# AFE1-2.net
KiCad netlist of a schematic drawn in Altium Designer
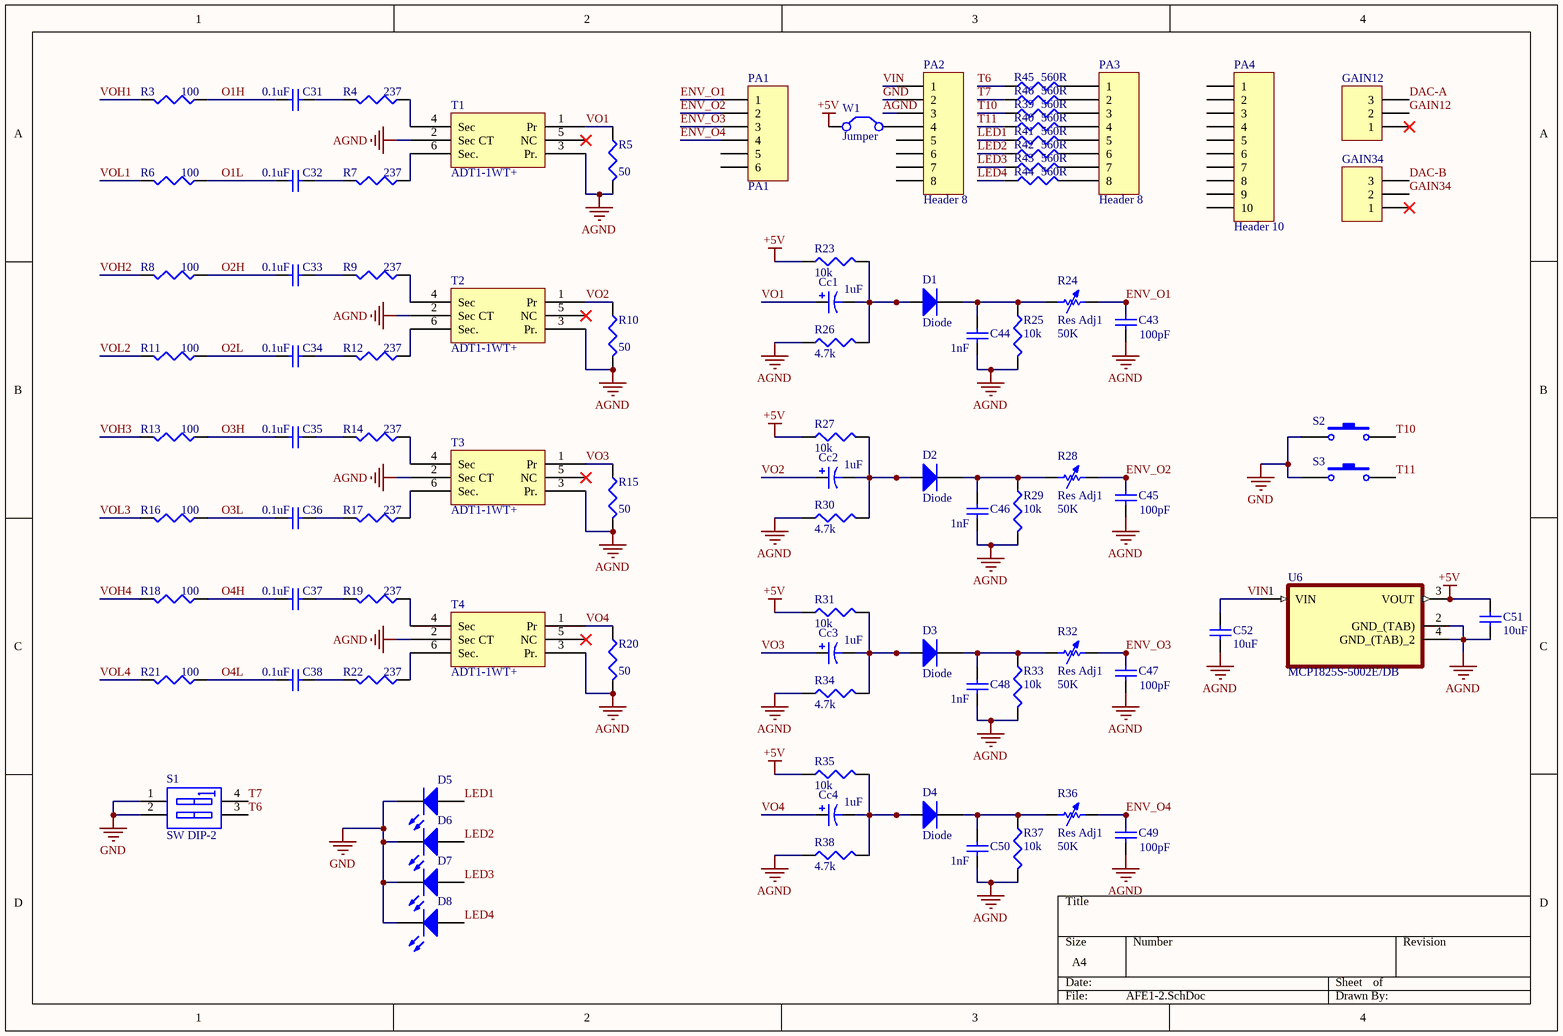
[diagram p0: AFE1-2.SchDoc]

(export (version "E")
  (design (tool "Eeschema 10.0.6"))
  (components
    (comp (ref "C31")
      (value "0.1uF")
      (footprint "1608[0603]")
      (description "Capacitor (Semiconductor SIM Model)")
      (fields (field (name "PUBLISHER") "Altium Limited"))
      (libsource (lib "Miscellaneous Devices") (part "Cap Semi"))
    )
    (comp (ref "C32")
      (value "0.1uF")
      (footprint "1608[0603]")
      (description "Capacitor (Semiconductor SIM Model)")
      (fields (field (name "PUBLISHER") "Altium Limited"))
      (libsource (lib "Miscellaneous Devices") (part "Cap Semi"))
    )
    (comp (ref "C33")
      (value "0.1uF")
      (footprint "1608[0603]")
      (description "Capacitor (Semiconductor SIM Model)")
      (fields (field (name "PUBLISHER") "Altium Limited"))
      (libsource (lib "Miscellaneous Devices") (part "Cap Semi"))
    )
    (comp (ref "C34")
      (value "0.1uF")
      (footprint "1608[0603]")
      (description "Capacitor (Semiconductor SIM Model)")
      (fields (field (name "PUBLISHER") "Altium Limited"))
      (libsource (lib "Miscellaneous Devices") (part "Cap Semi"))
    )
    (comp (ref "C35")
      (value "0.1uF")
      (footprint "1608[0603]")
      (description "Capacitor (Semiconductor SIM Model)")
      (fields (field (name "PUBLISHER") "Altium Limited"))
      (libsource (lib "Miscellaneous Devices") (part "Cap Semi"))
    )
    (comp (ref "C36")
      (value "0.1uF")
      (footprint "1608[0603]")
      (description "Capacitor (Semiconductor SIM Model)")
      (fields (field (name "PUBLISHER") "Altium Limited"))
      (libsource (lib "Miscellaneous Devices") (part "Cap Semi"))
    )
    (comp (ref "C37")
      (value "0.1uF")
      (footprint "1608[0603]")
      (description "Capacitor (Semiconductor SIM Model)")
      (fields (field (name "PUBLISHER") "Altium Limited"))
      (libsource (lib "Miscellaneous Devices") (part "Cap Semi"))
    )
    (comp (ref "C38")
      (value "0.1uF")
      (footprint "1608[0603]")
      (description "Capacitor (Semiconductor SIM Model)")
      (fields (field (name "PUBLISHER") "Altium Limited"))
      (libsource (lib "Miscellaneous Devices") (part "Cap Semi"))
    )
    (comp (ref "C43")
      (value "100pF")
      (footprint "1608[0603]")
      (description "Capacitor (Semiconductor SIM Model)")
      (fields (field (name "PUBLISHER") "Altium Limited"))
      (libsource (lib "Miscellaneous Devices") (part "Cap Semi"))
    )
    (comp (ref "C44")
      (value "1nF")
      (footprint "1608[0603]")
      (description "Capacitor (Semiconductor SIM Model)")
      (fields (field (name "PUBLISHER") "Altium Limited"))
      (libsource (lib "Miscellaneous Devices") (part "Cap Semi"))
    )
    (comp (ref "C45")
      (value "100pF")
      (footprint "1608[0603]")
      (description "Capacitor (Semiconductor SIM Model)")
      (fields (field (name "PUBLISHER") "Altium Limited"))
      (libsource (lib "Miscellaneous Devices") (part "Cap Semi"))
    )
    (comp (ref "C46")
      (value "1nF")
      (footprint "1608[0603]")
      (description "Capacitor (Semiconductor SIM Model)")
      (fields (field (name "PUBLISHER") "Altium Limited"))
      (libsource (lib "Miscellaneous Devices") (part "Cap Semi"))
    )
    (comp (ref "C47")
      (value "100pF")
      (footprint "1608[0603]")
      (description "Capacitor (Semiconductor SIM Model)")
      (fields (field (name "PUBLISHER") "Altium Limited"))
      (libsource (lib "Miscellaneous Devices") (part "Cap Semi"))
    )
    (comp (ref "C48")
      (value "1nF")
      (footprint "1608[0603]")
      (description "Capacitor (Semiconductor SIM Model)")
      (fields (field (name "PUBLISHER") "Altium Limited"))
      (libsource (lib "Miscellaneous Devices") (part "Cap Semi"))
    )
    (comp (ref "C49")
      (value "100pF")
      (footprint "1608[0603]")
      (description "Capacitor (Semiconductor SIM Model)")
      (fields (field (name "PUBLISHER") "Altium Limited"))
      (libsource (lib "Miscellaneous Devices") (part "Cap Semi"))
    )
    (comp (ref "C50")
      (value "1nF")
      (footprint "1608[0603]")
      (description "Capacitor (Semiconductor SIM Model)")
      (fields (field (name "PUBLISHER") "Altium Limited"))
      (libsource (lib "Miscellaneous Devices") (part "Cap Semi"))
    )
    (comp (ref "C51")
      (value "10uF")
      (footprint "6-0805_L")
      (description "Capacitor (Semiconductor SIM Model)")
      (fields (field (name "PUBLISHER") "Altium Limited"))
      (libsource (lib "Miscellaneous Devices") (part "Cap Semi"))
    )
    (comp (ref "C52")
      (value "10uF")
      (footprint "6-0805_L")
      (description "Capacitor (Semiconductor SIM Model)")
      (fields (field (name "PUBLISHER") "Altium Limited"))
      (libsource (lib "Miscellaneous Devices") (part "Cap Semi"))
    )
    (comp (ref "Cc1")
      (value "1uF")
      (footprint "C0805")
      (description "Polarized Capacitor (Surface Mount)")
      (fields (field (name "PUBLISHER") "Altium Limited"))
      (libsource (lib "Miscellaneous Devices") (part "Cap Pol3"))
    )
    (comp (ref "Cc2")
      (value "1uF")
      (footprint "C0805")
      (description "Polarized Capacitor (Surface Mount)")
      (fields (field (name "PUBLISHER") "Altium Limited"))
      (libsource (lib "Miscellaneous Devices") (part "Cap Pol3"))
    )
    (comp (ref "Cc3")
      (value "1uF")
      (footprint "C0805")
      (description "Polarized Capacitor (Surface Mount)")
      (fields (field (name "PUBLISHER") "Altium Limited"))
      (libsource (lib "Miscellaneous Devices") (part "Cap Pol3"))
    )
    (comp (ref "Cc4")
      (value "1uF")
      (footprint "C0805")
      (description "Polarized Capacitor (Surface Mount)")
      (fields (field (name "PUBLISHER") "Altium Limited"))
      (libsource (lib "Miscellaneous Devices") (part "Cap Pol3"))
    )
    (comp (ref "D1")
      (value "Diode")
      (footprint "Miscellaneous Devices:6-0805_L")
      (description "Default Diode")
      (fields (field (name "PUBLISHER") "Altium Limited"))
      (libsource (lib "Miscellaneous Devices") (part "Diode"))
    )
    (comp (ref "D2")
      (value "Diode")
      (footprint "Miscellaneous Devices:6-0805_L")
      (description "Default Diode")
      (fields (field (name "PUBLISHER") "Altium Limited"))
      (libsource (lib "Miscellaneous Devices") (part "Diode"))
    )
    (comp (ref "D3")
      (value "Diode")
      (footprint "Miscellaneous Devices:6-0805_L")
      (description "Default Diode")
      (fields (field (name "PUBLISHER") "Altium Limited"))
      (libsource (lib "Miscellaneous Devices") (part "Diode"))
    )
    (comp (ref "D4")
      (value "Diode")
      (footprint "Miscellaneous Devices:6-0805_L")
      (description "Default Diode")
      (fields (field (name "PUBLISHER") "Altium Limited"))
      (libsource (lib "Miscellaneous Devices") (part "Diode"))
    )
    (comp (ref "D5")
      (value "~")
      (footprint "6-0805_N")
      (description "Typical BLUE SiC LED")
      (fields (field (name "PUBLISHER") "Altium Limited"))
      (libsource (lib "Miscellaneous Devices") (part "LED3"))
    )
    (comp (ref "D6")
      (value "~")
      (footprint "6-0805_N")
      (description "Typical BLUE SiC LED")
      (fields (field (name "PUBLISHER") "Altium Limited"))
      (libsource (lib "Miscellaneous Devices") (part "LED3"))
    )
    (comp (ref "D7")
      (value "~")
      (footprint "6-0805_N")
      (description "Typical BLUE SiC LED")
      (fields (field (name "PUBLISHER") "Altium Limited"))
      (libsource (lib "Miscellaneous Devices") (part "LED3"))
    )
    (comp (ref "D8")
      (value "~")
      (footprint "6-0805_N")
      (description "Typical BLUE SiC LED")
      (fields (field (name "PUBLISHER") "Altium Limited"))
      (libsource (lib "Miscellaneous Devices") (part "LED3"))
    )
    (comp (ref "GAIN12")
      (value "~")
      (footprint "HDR1X3")
      (description "Header, 3-Pin")
      (fields (field (name "PUBLISHER") "Altium Limited"))
      (libsource (lib "Miscellaneous Connectors") (part "Header 3"))
    )
    (comp (ref "GAIN34")
      (value "~")
      (footprint "HDR1X3")
      (description "Header, 3-Pin")
      (fields (field (name "PUBLISHER") "Altium Limited"))
      (libsource (lib "Miscellaneous Connectors") (part "Header 3"))
    )
    (comp (ref "PA1")
      (value "PA1")
      (footprint "HDR1X6")
      (description "Header, 6-Pin")
      (fields (field (name "PUBLISHER") "Altium Limited"))
      (libsource (lib "Miscellaneous Connectors") (part "Header 6"))
    )
    (comp (ref "PA2")
      (value "Header 8")
      (footprint "HDR1X8")
      (description "Header, 8-Pin")
      (fields (field (name "PUBLISHER") "Altium Limited"))
      (libsource (lib "Miscellaneous Connectors") (part "Header 8"))
    )
    (comp (ref "PA3")
      (value "Header 8")
      (footprint "HDR1X8")
      (description "Header, 8-Pin")
      (fields (field (name "PUBLISHER") "Altium Limited"))
      (libsource (lib "Miscellaneous Connectors") (part "Header 8"))
    )
    (comp (ref "PA4")
      (value "Header 10")
      (footprint "HDR1X10")
      (description "Header, 10-Pin")
      (fields (field (name "PUBLISHER") "Altium Limited"))
      (libsource (lib "Miscellaneous Connectors") (part "Header 10"))
    )
    (comp (ref "R3")
      (value "100")
      (footprint "J1-0603")
      (description "Resistor")
      (fields (field (name "PUBLISHER") "Altium Limited"))
      (libsource (lib "Miscellaneous Devices") (part "Res3"))
    )
    (comp (ref "R4")
      (value "237")
      (footprint "J1-0603")
      (description "Resistor")
      (fields (field (name "PUBLISHER") "Altium Limited"))
      (libsource (lib "Miscellaneous Devices") (part "Res3"))
    )
    (comp (ref "R5")
      (value "50")
      (footprint "J1-0603")
      (description "Resistor")
      (fields (field (name "PUBLISHER") "Altium Limited"))
      (libsource (lib "Miscellaneous Devices") (part "Res3"))
    )
    (comp (ref "R6")
      (value "100")
      (footprint "J1-0603")
      (description "Resistor")
      (fields (field (name "PUBLISHER") "Altium Limited"))
      (libsource (lib "Miscellaneous Devices") (part "Res3"))
    )
    (comp (ref "R7")
      (value "237")
      (footprint "J1-0603")
      (description "Resistor")
      (fields (field (name "PUBLISHER") "Altium Limited"))
      (libsource (lib "Miscellaneous Devices") (part "Res3"))
    )
    (comp (ref "R8")
      (value "100")
      (footprint "J1-0603")
      (description "Resistor")
      (fields (field (name "PUBLISHER") "Altium Limited"))
      (libsource (lib "Miscellaneous Devices") (part "Res3"))
    )
    (comp (ref "R9")
      (value "237")
      (footprint "J1-0603")
      (description "Resistor")
      (fields (field (name "PUBLISHER") "Altium Limited"))
      (libsource (lib "Miscellaneous Devices") (part "Res3"))
    )
    (comp (ref "R10")
      (value "50")
      (footprint "J1-0603")
      (description "Resistor")
      (fields (field (name "PUBLISHER") "Altium Limited"))
      (libsource (lib "Miscellaneous Devices") (part "Res3"))
    )
    (comp (ref "R11")
      (value "100")
      (footprint "J1-0603")
      (description "Resistor")
      (fields (field (name "PUBLISHER") "Altium Limited"))
      (libsource (lib "Miscellaneous Devices") (part "Res3"))
    )
    (comp (ref "R12")
      (value "237")
      (footprint "J1-0603")
      (description "Resistor")
      (fields (field (name "PUBLISHER") "Altium Limited"))
      (libsource (lib "Miscellaneous Devices") (part "Res3"))
    )
    (comp (ref "R13")
      (value "100")
      (footprint "J1-0603")
      (description "Resistor")
      (fields (field (name "PUBLISHER") "Altium Limited"))
      (libsource (lib "Miscellaneous Devices") (part "Res3"))
    )
    (comp (ref "R14")
      (value "237")
      (footprint "J1-0603")
      (description "Resistor")
      (fields (field (name "PUBLISHER") "Altium Limited"))
      (libsource (lib "Miscellaneous Devices") (part "Res3"))
    )
    (comp (ref "R15")
      (value "50")
      (footprint "J1-0603")
      (description "Resistor")
      (fields (field (name "PUBLISHER") "Altium Limited"))
      (libsource (lib "Miscellaneous Devices") (part "Res3"))
    )
    (comp (ref "R16")
      (value "100")
      (footprint "J1-0603")
      (description "Resistor")
      (fields (field (name "PUBLISHER") "Altium Limited"))
      (libsource (lib "Miscellaneous Devices") (part "Res3"))
    )
    (comp (ref "R17")
      (value "237")
      (footprint "J1-0603")
      (description "Resistor")
      (fields (field (name "PUBLISHER") "Altium Limited"))
      (libsource (lib "Miscellaneous Devices") (part "Res3"))
    )
    (comp (ref "R18")
      (value "100")
      (footprint "J1-0603")
      (description "Resistor")
      (fields (field (name "PUBLISHER") "Altium Limited"))
      (libsource (lib "Miscellaneous Devices") (part "Res3"))
    )
    (comp (ref "R19")
      (value "237")
      (footprint "J1-0603")
      (description "Resistor")
      (fields (field (name "PUBLISHER") "Altium Limited"))
      (libsource (lib "Miscellaneous Devices") (part "Res3"))
    )
    (comp (ref "R20")
      (value "50")
      (footprint "J1-0603")
      (description "Resistor")
      (fields (field (name "PUBLISHER") "Altium Limited"))
      (libsource (lib "Miscellaneous Devices") (part "Res3"))
    )
    (comp (ref "R21")
      (value "100")
      (footprint "J1-0603")
      (description "Resistor")
      (fields (field (name "PUBLISHER") "Altium Limited"))
      (libsource (lib "Miscellaneous Devices") (part "Res3"))
    )
    (comp (ref "R22")
      (value "237")
      (footprint "J1-0603")
      (description "Resistor")
      (fields (field (name "PUBLISHER") "Altium Limited"))
      (libsource (lib "Miscellaneous Devices") (part "Res3"))
    )
    (comp (ref "R23")
      (value "10k")
      (footprint "J1-0603")
      (description "Resistor")
      (fields (field (name "PUBLISHER") "Altium Limited"))
      (libsource (lib "Miscellaneous Devices") (part "Res3"))
    )
    (comp (ref "R24")
      (value "Res Adj1")
      (footprint "RESC2012M")
      (description "Variable Resistor")
      (fields (field (name "ALTIUM_VALUE") "50K") (field (name "PUBLISHER") "Altium Limited"))
      (libsource (lib "Miscellaneous Devices") (part "Res Adj1"))
    )
    (comp (ref "R25")
      (value "10k")
      (footprint "J1-0603")
      (description "Resistor")
      (fields (field (name "PUBLISHER") "Altium Limited"))
      (libsource (lib "Miscellaneous Devices") (part "Res3"))
    )
    (comp (ref "R26")
      (value "4.7k")
      (footprint "J1-0603")
      (description "Resistor")
      (fields (field (name "PUBLISHER") "Altium Limited"))
      (libsource (lib "Miscellaneous Devices") (part "Res3"))
    )
    (comp (ref "R27")
      (value "10k")
      (footprint "J1-0603")
      (description "Resistor")
      (fields (field (name "PUBLISHER") "Altium Limited"))
      (libsource (lib "Miscellaneous Devices") (part "Res3"))
    )
    (comp (ref "R28")
      (value "Res Adj1")
      (footprint "RESC2012M")
      (description "Variable Resistor")
      (fields (field (name "ALTIUM_VALUE") "50K") (field (name "PUBLISHER") "Altium Limited"))
      (libsource (lib "Miscellaneous Devices") (part "Res Adj1"))
    )
    (comp (ref "R29")
      (value "10k")
      (footprint "J1-0603")
      (description "Resistor")
      (fields (field (name "PUBLISHER") "Altium Limited"))
      (libsource (lib "Miscellaneous Devices") (part "Res3"))
    )
    (comp (ref "R30")
      (value "4.7k")
      (footprint "J1-0603")
      (description "Resistor")
      (fields (field (name "PUBLISHER") "Altium Limited"))
      (libsource (lib "Miscellaneous Devices") (part "Res3"))
    )
    (comp (ref "R31")
      (value "10k")
      (footprint "J1-0603")
      (description "Resistor")
      (fields (field (name "PUBLISHER") "Altium Limited"))
      (libsource (lib "Miscellaneous Devices") (part "Res3"))
    )
    (comp (ref "R32")
      (value "Res Adj1")
      (footprint "RESC2012M")
      (description "Variable Resistor")
      (fields (field (name "ALTIUM_VALUE") "50K") (field (name "PUBLISHER") "Altium Limited"))
      (libsource (lib "Miscellaneous Devices") (part "Res Adj1"))
    )
    (comp (ref "R33")
      (value "10k")
      (footprint "J1-0603")
      (description "Resistor")
      (fields (field (name "PUBLISHER") "Altium Limited"))
      (libsource (lib "Miscellaneous Devices") (part "Res3"))
    )
    (comp (ref "R34")
      (value "4.7k")
      (footprint "J1-0603")
      (description "Resistor")
      (fields (field (name "PUBLISHER") "Altium Limited"))
      (libsource (lib "Miscellaneous Devices") (part "Res3"))
    )
    (comp (ref "R35")
      (value "10k")
      (footprint "J1-0603")
      (description "Resistor")
      (fields (field (name "PUBLISHER") "Altium Limited"))
      (libsource (lib "Miscellaneous Devices") (part "Res3"))
    )
    (comp (ref "R36")
      (value "Res Adj1")
      (footprint "RESC2012M")
      (description "Variable Resistor")
      (fields (field (name "ALTIUM_VALUE") "50K") (field (name "PUBLISHER") "Altium Limited"))
      (libsource (lib "Miscellaneous Devices") (part "Res Adj1"))
    )
    (comp (ref "R37")
      (value "10k")
      (footprint "J1-0603")
      (description "Resistor")
      (fields (field (name "PUBLISHER") "Altium Limited"))
      (libsource (lib "Miscellaneous Devices") (part "Res3"))
    )
    (comp (ref "R38")
      (value "4.7k")
      (footprint "J1-0603")
      (description "Resistor")
      (fields (field (name "PUBLISHER") "Altium Limited"))
      (libsource (lib "Miscellaneous Devices") (part "Res3"))
    )
    (comp (ref "R39")
      (value "560R")
      (footprint "J1-0603")
      (description "Resistor")
      (fields (field (name "PUBLISHER") "Altium Limited"))
      (libsource (lib "Miscellaneous Devices") (part "Res3"))
    )
    (comp (ref "R40")
      (value "560R")
      (footprint "J1-0603")
      (description "Resistor")
      (fields (field (name "PUBLISHER") "Altium Limited"))
      (libsource (lib "Miscellaneous Devices") (part "Res3"))
    )
    (comp (ref "R41")
      (value "560R")
      (footprint "J1-0603")
      (description "Resistor")
      (fields (field (name "PUBLISHER") "Altium Limited"))
      (libsource (lib "Miscellaneous Devices") (part "Res3"))
    )
    (comp (ref "R42")
      (value "560R")
      (footprint "J1-0603")
      (description "Resistor")
      (fields (field (name "PUBLISHER") "Altium Limited"))
      (libsource (lib "Miscellaneous Devices") (part "Res3"))
    )
    (comp (ref "R43")
      (value "560R")
      (footprint "J1-0603")
      (description "Resistor")
      (fields (field (name "PUBLISHER") "Altium Limited"))
      (libsource (lib "Miscellaneous Devices") (part "Res3"))
    )
    (comp (ref "R44")
      (value "560R")
      (footprint "J1-0603")
      (description "Resistor")
      (fields (field (name "PUBLISHER") "Altium Limited"))
      (libsource (lib "Miscellaneous Devices") (part "Res3"))
    )
    (comp (ref "R45")
      (value "560R")
      (footprint "J1-0603")
      (description "Resistor")
      (fields (field (name "PUBLISHER") "Altium Limited"))
      (libsource (lib "Miscellaneous Devices") (part "Res3"))
    )
    (comp (ref "R46")
      (value "560R")
      (footprint "J1-0603")
      (description "Resistor")
      (fields (field (name "PUBLISHER") "Altium Limited"))
      (libsource (lib "Miscellaneous Devices") (part "Res3"))
    )
    (comp (ref "S1")
      (value "SW DIP-2")
      (footprint "DIP-4")
      (description "DIP Switch, 2 Position, SPST")
      (fields (field (name "PUBLISHER") "Altium Limited"))
      (libsource (lib "Miscellaneous Devices") (part "SW DIP-2"))
    )
    (comp (ref "S2")
      (value "~")
      (footprint "PTS525SM08SMTR2LFS")
      (description "Switch")
      (fields (field (name "PUBLISHER") "Altium Limited"))
      (libsource (lib "Miscellaneous Devices") (part "SW-PB"))
    )
    (comp (ref "S3")
      (value "~")
      (footprint "PTS525SM08SMTR2LFS")
      (description "Switch")
      (fields (field (name "PUBLISHER") "Altium Limited"))
      (libsource (lib "Miscellaneous Devices") (part "SW-PB"))
    )
    (comp (ref "T1")
      (value "ADT1-1WT+")
      (footprint "ADT1-1WT+")
      (libsource (lib "ADT1-1WT+") (part "ADT1-1WT+"))
    )
    (comp (ref "T2")
      (value "ADT1-1WT+")
      (footprint "ADT1-1WT+")
      (libsource (lib "ADT1-1WT+") (part "ADT1-1WT+"))
    )
    (comp (ref "T3")
      (value "ADT1-1WT+")
      (footprint "ADT1-1WT+")
      (libsource (lib "ADT1-1WT+") (part "ADT1-1WT+"))
    )
    (comp (ref "T4")
      (value "ADT1-1WT+")
      (footprint "ADT1-1WT+")
      (libsource (lib "ADT1-1WT+") (part "ADT1-1WT+"))
    )
    (comp (ref "U6")
      (value "MCP1825S-5002E/DB")
      (footprint "MCP1825S-5002E_DB:SOT230P700X180-4N")
      (fields (field (name "MF") "{'manufacturer': u'Microchip'}"))
      (libsource (lib "*") (part "MCP1825S-5002E/DB"))
    )
    (comp (ref "W1")
      (value "Jumper")
      (footprint "RAD-0.1")
      (description "Jumper Wire")
      (fields (field (name "PUBLISHER") "Altium Limited"))
      (libsource (lib "Miscellaneous Devices") (part "Jumper"))
    )
  )
  (nets
    (net (code "1") (name "+5V") (class "Default")
      (node (ref "C51") (pin "1") (pinfunction "1_1") (pintype "passive"))
      (node (ref "R23") (pin "1") (pinfunction "1_1") (pintype "passive"))
      (node (ref "R27") (pin "1") (pinfunction "1_1") (pintype "passive"))
      (node (ref "R31") (pin "1") (pinfunction "1_1") (pintype "passive"))
      (node (ref "R35") (pin "1") (pinfunction "1_1") (pintype "passive"))
      (node (ref "U6") (pin "3") (pinfunction "VOUT_3") (pintype "output"))
      (node (ref "W1") (pin "1") (pinfunction "C1_1") (pintype "passive"))
    )
    (net (code "2") (name "/DAC-A") (class "Default")
      (node (ref "GAIN12") (pin "3") (pinfunction "3_3") (pintype "passive"))
    )
    (net (code "3") (name "/DAC-B") (class "Default")
      (node (ref "GAIN34") (pin "3") (pinfunction "3_3") (pintype "passive"))
    )
    (net (code "4") (name "/ENV_O1") (class "Default")
      (node (ref "C43") (pin "1") (pinfunction "1_1") (pintype "passive"))
      (node (ref "PA1") (pin "1") (pinfunction "1_1") (pintype "passive"))
      (node (ref "R24") (pin "2") (pinfunction "2_2") (pintype "passive"))
    )
    (net (code "5") (name "/ENV_O2") (class "Default")
      (node (ref "C45") (pin "1") (pinfunction "1_1") (pintype "passive"))
      (node (ref "PA1") (pin "2") (pinfunction "2_2") (pintype "passive"))
      (node (ref "R28") (pin "2") (pinfunction "2_2") (pintype "passive"))
    )
    (net (code "6") (name "/ENV_O3") (class "Default")
      (node (ref "C47") (pin "1") (pinfunction "1_1") (pintype "passive"))
      (node (ref "PA1") (pin "3") (pinfunction "3_3") (pintype "passive"))
      (node (ref "R32") (pin "2") (pinfunction "2_2") (pintype "passive"))
    )
    (net (code "7") (name "/ENV_O4") (class "Default")
      (node (ref "C49") (pin "1") (pinfunction "1_1") (pintype "passive"))
      (node (ref "PA1") (pin "4") (pinfunction "4_4") (pintype "passive"))
      (node (ref "R36") (pin "2") (pinfunction "2_2") (pintype "passive"))
    )
    (net (code "8") (name "/GAIN12") (class "Default")
      (node (ref "GAIN12") (pin "2") (pinfunction "2_2") (pintype "passive"))
    )
    (net (code "9") (name "/GAIN34") (class "Default")
      (node (ref "GAIN34") (pin "2") (pinfunction "2_2") (pintype "passive"))
    )
    (net (code "10") (name "/LED1") (class "Default")
      (node (ref "D5") (pin "1") (pinfunction "A_1") (pintype "passive"))
      (node (ref "R41") (pin "1") (pinfunction "1_1") (pintype "passive"))
    )
    (net (code "11") (name "/LED2") (class "Default")
      (node (ref "D6") (pin "1") (pinfunction "A_1") (pintype "passive"))
      (node (ref "R42") (pin "1") (pinfunction "1_1") (pintype "passive"))
    )
    (net (code "12") (name "/LED3") (class "Default")
      (node (ref "D7") (pin "1") (pinfunction "A_1") (pintype "passive"))
      (node (ref "R43") (pin "1") (pinfunction "1_1") (pintype "passive"))
    )
    (net (code "13") (name "/LED4") (class "Default")
      (node (ref "D8") (pin "1") (pinfunction "A_1") (pintype "passive"))
      (node (ref "R44") (pin "1") (pinfunction "1_1") (pintype "passive"))
    )
    (net (code "14") (name "/O1H") (class "Default")
      (node (ref "C31") (pin "1") (pinfunction "1_1") (pintype "passive"))
      (node (ref "R3") (pin "1") (pinfunction "1_1") (pintype "passive"))
    )
    (net (code "15") (name "/O1L") (class "Default")
      (node (ref "C32") (pin "1") (pinfunction "1_1") (pintype "passive"))
      (node (ref "R6") (pin "1") (pinfunction "1_1") (pintype "passive"))
    )
    (net (code "16") (name "/O2H") (class "Default")
      (node (ref "C33") (pin "1") (pinfunction "1_1") (pintype "passive"))
      (node (ref "R8") (pin "1") (pinfunction "1_1") (pintype "passive"))
    )
    (net (code "17") (name "/O2L") (class "Default")
      (node (ref "C34") (pin "1") (pinfunction "1_1") (pintype "passive"))
      (node (ref "R11") (pin "1") (pinfunction "1_1") (pintype "passive"))
    )
    (net (code "18") (name "/O3H") (class "Default")
      (node (ref "C35") (pin "1") (pinfunction "1_1") (pintype "passive"))
      (node (ref "R13") (pin "1") (pinfunction "1_1") (pintype "passive"))
    )
    (net (code "19") (name "/O3L") (class "Default")
      (node (ref "C36") (pin "1") (pinfunction "1_1") (pintype "passive"))
      (node (ref "R16") (pin "1") (pinfunction "1_1") (pintype "passive"))
    )
    (net (code "20") (name "/O4H") (class "Default")
      (node (ref "C37") (pin "1") (pinfunction "1_1") (pintype "passive"))
      (node (ref "R18") (pin "1") (pinfunction "1_1") (pintype "passive"))
    )
    (net (code "21") (name "/O4L") (class "Default")
      (node (ref "C38") (pin "1") (pinfunction "1_1") (pintype "passive"))
      (node (ref "R21") (pin "1") (pinfunction "1_1") (pintype "passive"))
    )
    (net (code "22") (name "/T6") (class "Default")
      (node (ref "R45") (pin "1") (pinfunction "1_1") (pintype "passive"))
      (node (ref "S1") (pin "3") (pinfunction "B2_3") (pintype "passive"))
    )
    (net (code "23") (name "/T7") (class "Default")
      (node (ref "R46") (pin "1") (pinfunction "1_1") (pintype "passive"))
      (node (ref "S1") (pin "4") (pinfunction "B1_4") (pintype "passive"))
    )
    (net (code "24") (name "/T10") (class "Default")
      (node (ref "R39") (pin "1") (pinfunction "1_1") (pintype "passive"))
      (node (ref "S2") (pin "2") (pinfunction "2_2") (pintype "passive"))
    )
    (net (code "25") (name "/T11") (class "Default")
      (node (ref "R40") (pin "1") (pinfunction "1_1") (pintype "passive"))
      (node (ref "S3") (pin "2") (pinfunction "2_2") (pintype "passive"))
    )
    (net (code "26") (name "/VIN") (class "Default")
      (node (ref "C52") (pin "1") (pinfunction "1_1") (pintype "passive"))
      (node (ref "PA2") (pin "1") (pinfunction "1_1") (pintype "passive"))
      (node (ref "U6") (pin "1") (pinfunction "VIN_1") (pintype "input"))
    )
    (net (code "27") (name "/VO1") (class "Default")
      (node (ref "Cc1") (pin "1") (pinfunction "1_1") (pintype "passive"))
      (node (ref "R5") (pin "1") (pinfunction "1_1") (pintype "passive"))
      (node (ref "T1") (pin "1") (pinfunction "Pr_1") (pintype "passive"))
    )
    (net (code "28") (name "/VO2") (class "Default")
      (node (ref "Cc2") (pin "1") (pinfunction "1_1") (pintype "passive"))
      (node (ref "R10") (pin "1") (pinfunction "1_1") (pintype "passive"))
      (node (ref "T2") (pin "1") (pinfunction "Pr_1") (pintype "passive"))
    )
    (net (code "29") (name "/VO3") (class "Default")
      (node (ref "Cc3") (pin "1") (pinfunction "1_1") (pintype "passive"))
      (node (ref "R15") (pin "1") (pinfunction "1_1") (pintype "passive"))
      (node (ref "T3") (pin "1") (pinfunction "Pr_1") (pintype "passive"))
    )
    (net (code "30") (name "/VO4") (class "Default")
      (node (ref "Cc4") (pin "1") (pinfunction "1_1") (pintype "passive"))
      (node (ref "R20") (pin "1") (pinfunction "1_1") (pintype "passive"))
      (node (ref "T4") (pin "1") (pinfunction "Pr_1") (pintype "passive"))
    )
    (net (code "31") (name "/VOH1") (class "Default")
      (node (ref "R3") (pin "2") (pinfunction "2_2") (pintype "passive"))
    )
    (net (code "32") (name "/VOH2") (class "Default")
      (node (ref "R8") (pin "2") (pinfunction "2_2") (pintype "passive"))
    )
    (net (code "33") (name "/VOH3") (class "Default")
      (node (ref "R13") (pin "2") (pinfunction "2_2") (pintype "passive"))
    )
    (net (code "34") (name "/VOH4") (class "Default")
      (node (ref "R18") (pin "2") (pinfunction "2_2") (pintype "passive"))
    )
    (net (code "35") (name "/VOL1") (class "Default")
      (node (ref "R6") (pin "2") (pinfunction "2_2") (pintype "passive"))
    )
    (net (code "36") (name "/VOL2") (class "Default")
      (node (ref "R11") (pin "2") (pinfunction "2_2") (pintype "passive"))
    )
    (net (code "37") (name "/VOL3") (class "Default")
      (node (ref "R16") (pin "2") (pinfunction "2_2") (pintype "passive"))
    )
    (net (code "38") (name "/VOL4") (class "Default")
      (node (ref "R21") (pin "2") (pinfunction "2_2") (pintype "passive"))
    )
    (net (code "39") (name "AGND") (class "Default")
      (node (ref "C43") (pin "2") (pinfunction "2_2") (pintype "passive"))
      (node (ref "C44") (pin "2") (pinfunction "2_2") (pintype "passive"))
      (node (ref "C45") (pin "2") (pinfunction "2_2") (pintype "passive"))
      (node (ref "C46") (pin "2") (pinfunction "2_2") (pintype "passive"))
      (node (ref "C47") (pin "2") (pinfunction "2_2") (pintype "passive"))
      (node (ref "C48") (pin "2") (pinfunction "2_2") (pintype "passive"))
      (node (ref "C49") (pin "2") (pinfunction "2_2") (pintype "passive"))
      (node (ref "C50") (pin "2") (pinfunction "2_2") (pintype "passive"))
      (node (ref "C51") (pin "2") (pinfunction "2_2") (pintype "passive"))
      (node (ref "C52") (pin "2") (pinfunction "2_2") (pintype "passive"))
      (node (ref "PA2") (pin "3") (pinfunction "3_3") (pintype "passive"))
      (node (ref "R10") (pin "2") (pinfunction "2_2") (pintype "passive"))
      (node (ref "R15") (pin "2") (pinfunction "2_2") (pintype "passive"))
      (node (ref "R20") (pin "2") (pinfunction "2_2") (pintype "passive"))
      (node (ref "R25") (pin "2") (pinfunction "2_2") (pintype "passive"))
      (node (ref "R26") (pin "1") (pinfunction "1_1") (pintype "passive"))
      (node (ref "R29") (pin "2") (pinfunction "2_2") (pintype "passive"))
      (node (ref "R30") (pin "1") (pinfunction "1_1") (pintype "passive"))
      (node (ref "R33") (pin "2") (pinfunction "2_2") (pintype "passive"))
      (node (ref "R34") (pin "1") (pinfunction "1_1") (pintype "passive"))
      (node (ref "R37") (pin "2") (pinfunction "2_2") (pintype "passive"))
      (node (ref "R38") (pin "1") (pinfunction "1_1") (pintype "passive"))
      (node (ref "R5") (pin "2") (pinfunction "2_2") (pintype "passive"))
      (node (ref "T1") (pin "2") (pinfunction "Sec_CT_2") (pintype "passive"))
      (node (ref "T1") (pin "3") (pinfunction "Pr._3") (pintype "passive"))
      (node (ref "T2") (pin "2") (pinfunction "Sec_CT_2") (pintype "passive"))
      (node (ref "T2") (pin "3") (pinfunction "Pr._3") (pintype "passive"))
      (node (ref "T3") (pin "2") (pinfunction "Sec_CT_2") (pintype "passive"))
      (node (ref "T3") (pin "3") (pinfunction "Pr._3") (pintype "passive"))
      (node (ref "T4") (pin "2") (pinfunction "Sec_CT_2") (pintype "passive"))
      (node (ref "T4") (pin "3") (pinfunction "Pr._3") (pintype "passive"))
      (node (ref "U6") (pin "2") (pinfunction "GND_(TAB)_2") (pintype "power_in"))
      (node (ref "U6") (pin "4") (pinfunction "GND_(TAB)_2_4") (pintype "power_in"))
    )
    (net (code "40") (name "GND") (class "Default")
      (node (ref "D5") (pin "2") (pinfunction "K_2") (pintype "passive"))
      (node (ref "D6") (pin "2") (pinfunction "K_2") (pintype "passive"))
      (node (ref "D7") (pin "2") (pinfunction "K_2") (pintype "passive"))
      (node (ref "D8") (pin "2") (pinfunction "K_2") (pintype "passive"))
      (node (ref "PA2") (pin "2") (pinfunction "2_2") (pintype "passive"))
      (node (ref "S1") (pin "1") (pinfunction "A1_1") (pintype "passive"))
      (node (ref "S1") (pin "2") (pinfunction "A2_2") (pintype "passive"))
      (node (ref "S2") (pin "1") (pinfunction "1_1") (pintype "passive"))
      (node (ref "S3") (pin "1") (pinfunction "1_1") (pintype "passive"))
    )
    (net (code "41") (name "Net-(C31-Pad2)") (class "Default")
      (node (ref "C31") (pin "2") (pinfunction "2_2") (pintype "passive"))
      (node (ref "R4") (pin "2") (pinfunction "2_2") (pintype "passive"))
    )
    (net (code "42") (name "Net-(C32-Pad2)") (class "Default")
      (node (ref "C32") (pin "2") (pinfunction "2_2") (pintype "passive"))
      (node (ref "R7") (pin "2") (pinfunction "2_2") (pintype "passive"))
    )
    (net (code "43") (name "Net-(C33-Pad2)") (class "Default")
      (node (ref "C33") (pin "2") (pinfunction "2_2") (pintype "passive"))
      (node (ref "R9") (pin "2") (pinfunction "2_2") (pintype "passive"))
    )
    (net (code "44") (name "Net-(C34-Pad2)") (class "Default")
      (node (ref "C34") (pin "2") (pinfunction "2_2") (pintype "passive"))
      (node (ref "R12") (pin "2") (pinfunction "2_2") (pintype "passive"))
    )
    (net (code "45") (name "Net-(C35-Pad2)") (class "Default")
      (node (ref "C35") (pin "2") (pinfunction "2_2") (pintype "passive"))
      (node (ref "R14") (pin "2") (pinfunction "2_2") (pintype "passive"))
    )
    (net (code "46") (name "Net-(C36-Pad2)") (class "Default")
      (node (ref "C36") (pin "2") (pinfunction "2_2") (pintype "passive"))
      (node (ref "R17") (pin "2") (pinfunction "2_2") (pintype "passive"))
    )
    (net (code "47") (name "Net-(C37-Pad2)") (class "Default")
      (node (ref "C37") (pin "2") (pinfunction "2_2") (pintype "passive"))
      (node (ref "R19") (pin "2") (pinfunction "2_2") (pintype "passive"))
    )
    (net (code "48") (name "Net-(C38-Pad2)") (class "Default")
      (node (ref "C38") (pin "2") (pinfunction "2_2") (pintype "passive"))
      (node (ref "R22") (pin "2") (pinfunction "2_2") (pintype "passive"))
    )
    (net (code "49") (name "Net-(D1-A)") (class "Default")
      (node (ref "Cc1") (pin "2") (pinfunction "2_2") (pintype "passive"))
      (node (ref "D1") (pin "1") (pinfunction "A_1") (pintype "passive"))
      (node (ref "R23") (pin "2") (pinfunction "2_2") (pintype "passive"))
      (node (ref "R26") (pin "2") (pinfunction "2_2") (pintype "passive"))
    )
    (net (code "50") (name "Net-(D1-K)") (class "Default")
      (node (ref "C44") (pin "1") (pinfunction "1_1") (pintype "passive"))
      (node (ref "D1") (pin "2") (pinfunction "K_2") (pintype "passive"))
      (node (ref "R24") (pin "1") (pinfunction "1_1") (pintype "passive"))
      (node (ref "R25") (pin "1") (pinfunction "1_1") (pintype "passive"))
    )
    (net (code "51") (name "Net-(D2-A)") (class "Default")
      (node (ref "Cc2") (pin "2") (pinfunction "2_2") (pintype "passive"))
      (node (ref "D2") (pin "1") (pinfunction "A_1") (pintype "passive"))
      (node (ref "R27") (pin "2") (pinfunction "2_2") (pintype "passive"))
      (node (ref "R30") (pin "2") (pinfunction "2_2") (pintype "passive"))
    )
    (net (code "52") (name "Net-(D2-K)") (class "Default")
      (node (ref "C46") (pin "1") (pinfunction "1_1") (pintype "passive"))
      (node (ref "D2") (pin "2") (pinfunction "K_2") (pintype "passive"))
      (node (ref "R28") (pin "1") (pinfunction "1_1") (pintype "passive"))
      (node (ref "R29") (pin "1") (pinfunction "1_1") (pintype "passive"))
    )
    (net (code "53") (name "Net-(D3-A)") (class "Default")
      (node (ref "Cc3") (pin "2") (pinfunction "2_2") (pintype "passive"))
      (node (ref "D3") (pin "1") (pinfunction "A_1") (pintype "passive"))
      (node (ref "R31") (pin "2") (pinfunction "2_2") (pintype "passive"))
      (node (ref "R34") (pin "2") (pinfunction "2_2") (pintype "passive"))
    )
    (net (code "54") (name "Net-(D3-K)") (class "Default")
      (node (ref "C48") (pin "1") (pinfunction "1_1") (pintype "passive"))
      (node (ref "D3") (pin "2") (pinfunction "K_2") (pintype "passive"))
      (node (ref "R32") (pin "1") (pinfunction "1_1") (pintype "passive"))
      (node (ref "R33") (pin "1") (pinfunction "1_1") (pintype "passive"))
    )
    (net (code "55") (name "Net-(D4-A)") (class "Default")
      (node (ref "Cc4") (pin "2") (pinfunction "2_2") (pintype "passive"))
      (node (ref "D4") (pin "1") (pinfunction "A_1") (pintype "passive"))
      (node (ref "R35") (pin "2") (pinfunction "2_2") (pintype "passive"))
      (node (ref "R38") (pin "2") (pinfunction "2_2") (pintype "passive"))
    )
    (net (code "56") (name "Net-(D4-K)") (class "Default")
      (node (ref "C50") (pin "1") (pinfunction "1_1") (pintype "passive"))
      (node (ref "D4") (pin "2") (pinfunction "K_2") (pintype "passive"))
      (node (ref "R36") (pin "1") (pinfunction "1_1") (pintype "passive"))
      (node (ref "R37") (pin "1") (pinfunction "1_1") (pintype "passive"))
    )
    (net (code "57") (name "Net-(PA3-Pad1)") (class "Default")
      (node (ref "PA3") (pin "1") (pinfunction "1_1") (pintype "passive"))
      (node (ref "R45") (pin "2") (pinfunction "2_2") (pintype "passive"))
    )
    (net (code "58") (name "Net-(PA3-Pad2)") (class "Default")
      (node (ref "PA3") (pin "2") (pinfunction "2_2") (pintype "passive"))
      (node (ref "R46") (pin "2") (pinfunction "2_2") (pintype "passive"))
    )
    (net (code "59") (name "Net-(PA3-Pad3)") (class "Default")
      (node (ref "PA3") (pin "3") (pinfunction "3_3") (pintype "passive"))
      (node (ref "R39") (pin "2") (pinfunction "2_2") (pintype "passive"))
    )
    (net (code "60") (name "Net-(PA3-Pad4)") (class "Default")
      (node (ref "PA3") (pin "4") (pinfunction "4_4") (pintype "passive"))
      (node (ref "R40") (pin "2") (pinfunction "2_2") (pintype "passive"))
    )
    (net (code "61") (name "Net-(PA3-Pad5)") (class "Default")
      (node (ref "PA3") (pin "5") (pinfunction "5_5") (pintype "passive"))
      (node (ref "R41") (pin "2") (pinfunction "2_2") (pintype "passive"))
    )
    (net (code "62") (name "Net-(PA3-Pad6)") (class "Default")
      (node (ref "PA3") (pin "6") (pinfunction "6_6") (pintype "passive"))
      (node (ref "R42") (pin "2") (pinfunction "2_2") (pintype "passive"))
    )
    (net (code "63") (name "Net-(PA3-Pad7)") (class "Default")
      (node (ref "PA3") (pin "7") (pinfunction "7_7") (pintype "passive"))
      (node (ref "R43") (pin "2") (pinfunction "2_2") (pintype "passive"))
    )
    (net (code "64") (name "Net-(PA3-Pad8)") (class "Default")
      (node (ref "PA3") (pin "8") (pinfunction "8_8") (pintype "passive"))
      (node (ref "R44") (pin "2") (pinfunction "2_2") (pintype "passive"))
    )
    (net (code "65") (name "Net-(T1-Sec)") (class "Default")
      (node (ref "R4") (pin "1") (pinfunction "1_1") (pintype "passive"))
      (node (ref "T1") (pin "4") (pinfunction "Sec_4") (pintype "passive"))
    )
    (net (code "66") (name "Net-(T1-Sec.)") (class "Default")
      (node (ref "R7") (pin "1") (pinfunction "1_1") (pintype "passive"))
      (node (ref "T1") (pin "6") (pinfunction "Sec._6") (pintype "passive"))
    )
    (net (code "67") (name "Net-(T2-Sec)") (class "Default")
      (node (ref "R9") (pin "1") (pinfunction "1_1") (pintype "passive"))
      (node (ref "T2") (pin "4") (pinfunction "Sec_4") (pintype "passive"))
    )
    (net (code "68") (name "Net-(T2-Sec.)") (class "Default")
      (node (ref "R12") (pin "1") (pinfunction "1_1") (pintype "passive"))
      (node (ref "T2") (pin "6") (pinfunction "Sec._6") (pintype "passive"))
    )
    (net (code "69") (name "Net-(T3-Sec)") (class "Default")
      (node (ref "R14") (pin "1") (pinfunction "1_1") (pintype "passive"))
      (node (ref "T3") (pin "4") (pinfunction "Sec_4") (pintype "passive"))
    )
    (net (code "70") (name "Net-(T3-Sec.)") (class "Default")
      (node (ref "R17") (pin "1") (pinfunction "1_1") (pintype "passive"))
      (node (ref "T3") (pin "6") (pinfunction "Sec._6") (pintype "passive"))
    )
    (net (code "71") (name "Net-(T4-Sec)") (class "Default")
      (node (ref "R19") (pin "1") (pinfunction "1_1") (pintype "passive"))
      (node (ref "T4") (pin "4") (pinfunction "Sec_4") (pintype "passive"))
    )
    (net (code "72") (name "Net-(T4-Sec.)") (class "Default")
      (node (ref "R22") (pin "1") (pinfunction "1_1") (pintype "passive"))
      (node (ref "T4") (pin "6") (pinfunction "Sec._6") (pintype "passive"))
    )
    (net (code "73") (name "Net-(W1-C2)") (class "Default")
      (node (ref "PA2") (pin "4") (pinfunction "4_4") (pintype "passive"))
      (node (ref "W1") (pin "2") (pinfunction "C2_2") (pintype "passive"))
    )
    (net (code "74") (name "unconnected-(GAIN12-Pad1)") (class "Default")
      (node (ref "GAIN12") (pin "1") (pinfunction "1_1") (pintype "passive+no_connect"))
    )
    (net (code "75") (name "unconnected-(GAIN34-Pad1)") (class "Default")
      (node (ref "GAIN34") (pin "1") (pinfunction "1_1") (pintype "passive+no_connect"))
    )
    (net (code "76") (name "unconnected-(PA1-Pad5)") (class "Default")
      (node (ref "PA1") (pin "5") (pinfunction "5_5") (pintype "passive"))
    )
    (net (code "77") (name "unconnected-(PA1-Pad6)") (class "Default")
      (node (ref "PA1") (pin "6") (pinfunction "6_6") (pintype "passive"))
    )
    (net (code "78") (name "unconnected-(PA2-Pad5)") (class "Default")
      (node (ref "PA2") (pin "5") (pinfunction "5_5") (pintype "passive"))
    )
    (net (code "79") (name "unconnected-(PA2-Pad6)") (class "Default")
      (node (ref "PA2") (pin "6") (pinfunction "6_6") (pintype "passive"))
    )
    (net (code "80") (name "unconnected-(PA2-Pad7)") (class "Default")
      (node (ref "PA2") (pin "7") (pinfunction "7_7") (pintype "passive"))
    )
    (net (code "81") (name "unconnected-(PA2-Pad8)") (class "Default")
      (node (ref "PA2") (pin "8") (pinfunction "8_8") (pintype "passive"))
    )
    (net (code "82") (name "unconnected-(PA4-Pad1)") (class "Default")
      (node (ref "PA4") (pin "1") (pinfunction "1_1") (pintype "passive"))
    )
    (net (code "83") (name "unconnected-(PA4-Pad2)") (class "Default")
      (node (ref "PA4") (pin "2") (pinfunction "2_2") (pintype "passive"))
    )
    (net (code "84") (name "unconnected-(PA4-Pad3)") (class "Default")
      (node (ref "PA4") (pin "3") (pinfunction "3_3") (pintype "passive"))
    )
    (net (code "85") (name "unconnected-(PA4-Pad4)") (class "Default")
      (node (ref "PA4") (pin "4") (pinfunction "4_4") (pintype "passive"))
    )
    (net (code "86") (name "unconnected-(PA4-Pad5)") (class "Default")
      (node (ref "PA4") (pin "5") (pinfunction "5_5") (pintype "passive"))
    )
    (net (code "87") (name "unconnected-(PA4-Pad6)") (class "Default")
      (node (ref "PA4") (pin "6") (pinfunction "6_6") (pintype "passive"))
    )
    (net (code "88") (name "unconnected-(PA4-Pad7)") (class "Default")
      (node (ref "PA4") (pin "7") (pinfunction "7_7") (pintype "passive"))
    )
    (net (code "89") (name "unconnected-(PA4-Pad8)") (class "Default")
      (node (ref "PA4") (pin "8") (pinfunction "8_8") (pintype "passive"))
    )
    (net (code "90") (name "unconnected-(PA4-Pad9)") (class "Default")
      (node (ref "PA4") (pin "9") (pinfunction "9_9") (pintype "passive"))
    )
    (net (code "91") (name "unconnected-(PA4-Pad10)") (class "Default")
      (node (ref "PA4") (pin "10") (pinfunction "10_10") (pintype "passive"))
    )
    (net (code "92") (name "unconnected-(T1-NC-Pad5)") (class "Default")
      (node (ref "T1") (pin "5") (pinfunction "NC_5") (pintype "passive+no_connect"))
    )
    (net (code "93") (name "unconnected-(T2-NC-Pad5)") (class "Default")
      (node (ref "T2") (pin "5") (pinfunction "NC_5") (pintype "passive+no_connect"))
    )
    (net (code "94") (name "unconnected-(T3-NC-Pad5)") (class "Default")
      (node (ref "T3") (pin "5") (pinfunction "NC_5") (pintype "passive+no_connect"))
    )
    (net (code "95") (name "unconnected-(T4-NC-Pad5)") (class "Default")
      (node (ref "T4") (pin "5") (pinfunction "NC_5") (pintype "passive+no_connect"))
    )
  )
)
